# Amp_1watt_30MHz_2700MHz.net
KiCad netlist of a schematic drawn in Altium Designer
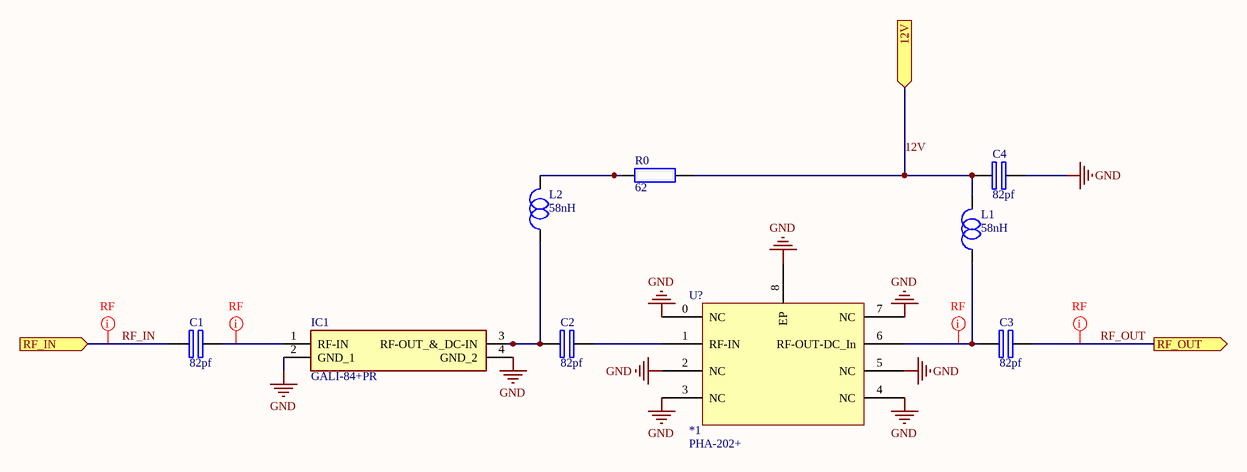
[diagram p0: Amp_1watt_30MHz_2700MHz.SchDoc]

(export (version "E")
  (design (tool "Eeschema 10.0.6"))
  (components
    (comp (ref "*1")
      (value "PHA-202+")
      (footprint "PHA-202+")
      (libsource (lib "Integrated_Library1") (part "PHA-202+"))
    )
    (comp (ref "C1")
      (value "82pf")
      (footprint "CAPC0603X08N")
      (description "The capacitor have 2PIN in AXIAL and SMD models.\r\nall non-polar models include.")
      (fields (field (name "CREATOR") "Shahab Azmoodeh") (field (name "CREATED FOR") "HiroNegarPars"))
      (libsource (lib "HiroNegarParsMainLib") (part "Capacitor2P-NP"))
    )
    (comp (ref "C2")
      (value "82pf")
      (footprint "CAPC0603X08N")
      (description "The capacitor have 2PIN in AXIAL and SMD models.\r\nall non-polar models include.")
      (fields (field (name "CREATOR") "Shahab Azmoodeh") (field (name "CREATED FOR") "HiroNegarPars"))
      (libsource (lib "HiroNegarParsMainLib") (part "Capacitor2P-NP"))
    )
    (comp (ref "C3")
      (value "82pf")
      (footprint "CAPC0603X08M")
      (description "The capacitor have 2PIN in AXIAL and SMD models.\r\nall non-polar models include.")
      (fields (field (name "CREATOR") "Shahab Azmoodeh") (field (name "CREATED FOR") "HiroNegarPars"))
      (libsource (lib "HiroNegarParsMainLib") (part "Capacitor2P-NP"))
    )
    (comp (ref "C4")
      (value "82pf")
      (footprint "CAPC0603X08M")
      (description "The capacitor have 2PIN in AXIAL and SMD models.\r\nall non-polar models include.")
      (fields (field (name "CREATOR") "Shahab Azmoodeh") (field (name "CREATED FOR") "HiroNegarPars"))
      (libsource (lib "HiroNegarParsMainLib") (part "Capacitor2P-NP"))
    )
    (comp (ref "IC1")
      (value "GALI-84+PR")
      (footprint "SamacSys:GALI5")
      (description "Integrated Circuit")
      (libsource (lib "*") (part "GALI-84+PR"))
    )
    (comp (ref "L1")
      (value "58nH")
      (footprint "INDC0805X142-2M")
      (description "generic smd and dip inductors")
      (fields (field (name "CREATOR") "Milad Mohammadi Bidhandi") (field (name "CREATED FOR") "Hiro Negar"))
      (libsource (lib "HiroNegarParsMainLib") (part "Inductor2P"))
    )
    (comp (ref "L2")
      (value "58nH")
      (footprint "INDC0805X142-2M")
      (description "generic smd and dip inductors")
      (fields (field (name "CREATOR") "Milad Mohammadi Bidhandi") (field (name "CREATED FOR") "Hiro Negar"))
      (libsource (lib "HiroNegarParsMainLib") (part "Inductor2P"))
    )
    (comp (ref "R0")
      (value "62")
      (footprint "RESC0603X04M")
      (description "The resistors have 2PIN in AXIAL and SMD models.\r\nAll wattage include in.")
      (fields (field (name "CREATOR") "Shahab Azmoodeh") (field (name "CREATED FOR") "HiroNegarPars"))
      (libsource (lib "HiroNegarParsMainLib") (part "Resistor2P"))
    )
  )
  (nets
    (net (code "1") (name "/12V") (class "Default")
      (node (ref "C4") (pin "1") (pinfunction "1_1") (pintype "passive"))
      (node (ref "L1") (pin "2") (pinfunction "2_2") (pintype "passive"))
      (node (ref "R0") (pin "2") (pinfunction "2_2") (pintype "passive"))
    )
    (net (code "2") (name "/RF_IN") (class "Default")
      (node (ref "C1") (pin "1") (pinfunction "1_1") (pintype "passive"))
    )
    (net (code "3") (name "/RF_OUT") (class "Default")
      (node (ref "C3") (pin "2") (pinfunction "2_2") (pintype "passive"))
    )
    (net (code "4") (name "GND") (class "Default")
      (node (ref "*1") (pin "0") (pinfunction "NC_0") (pintype "passive"))
      (node (ref "*1") (pin "2") (pinfunction "NC_2") (pintype "passive"))
      (node (ref "*1") (pin "3") (pinfunction "NC_3") (pintype "passive"))
      (node (ref "*1") (pin "4") (pinfunction "NC_4") (pintype "passive"))
      (node (ref "*1") (pin "5") (pinfunction "NC_5") (pintype "passive"))
      (node (ref "*1") (pin "7") (pinfunction "NC_7") (pintype "passive"))
      (node (ref "*1") (pin "8") (pinfunction "EP_8") (pintype "passive"))
      (node (ref "C4") (pin "2") (pinfunction "2_2") (pintype "passive"))
      (node (ref "IC1") (pin "2") (pinfunction "GND_1_2") (pintype "passive"))
      (node (ref "IC1") (pin "4") (pinfunction "GND_2_4") (pintype "passive"))
    )
    (net (code "5") (name "Net-(*1-RF-IN)") (class "Default")
      (node (ref "*1") (pin "1") (pinfunction "RF-IN_1") (pintype "passive"))
      (node (ref "C2") (pin "2") (pinfunction "2_2") (pintype "passive"))
    )
    (net (code "6") (name "Net-(*1-RF-OUT-DC_In)") (class "Default")
      (node (ref "*1") (pin "6") (pinfunction "RF-OUT-DC_In_6") (pintype "passive"))
      (node (ref "C3") (pin "1") (pinfunction "1_1") (pintype "passive"))
      (node (ref "L1") (pin "1") (pinfunction "1_1") (pintype "passive"))
    )
    (net (code "7") (name "Net-(IC1-RF-IN)") (class "Default")
      (node (ref "C1") (pin "2") (pinfunction "2_2") (pintype "passive"))
      (node (ref "IC1") (pin "1") (pinfunction "RF-IN_1") (pintype "passive"))
    )
    (net (code "8") (name "Net-(IC1-RF-OUT_&_DC-IN)") (class "Default")
      (node (ref "C2") (pin "1") (pinfunction "1_1") (pintype "passive"))
      (node (ref "IC1") (pin "3") (pinfunction "RF-OUT_&_DC-IN_3") (pintype "passive"))
      (node (ref "L2") (pin "1") (pinfunction "1_1") (pintype "passive"))
    )
    (net (code "9") (name "Net-(L2-Pad2)") (class "Default")
      (node (ref "L2") (pin "2") (pinfunction "2_2") (pintype "passive"))
      (node (ref "R0") (pin "1") (pinfunction "1_1") (pintype "passive"))
    )
  )
)
